# tactile_sensor_master.net
KiCad netlist of a schematic drawn in EAGLE
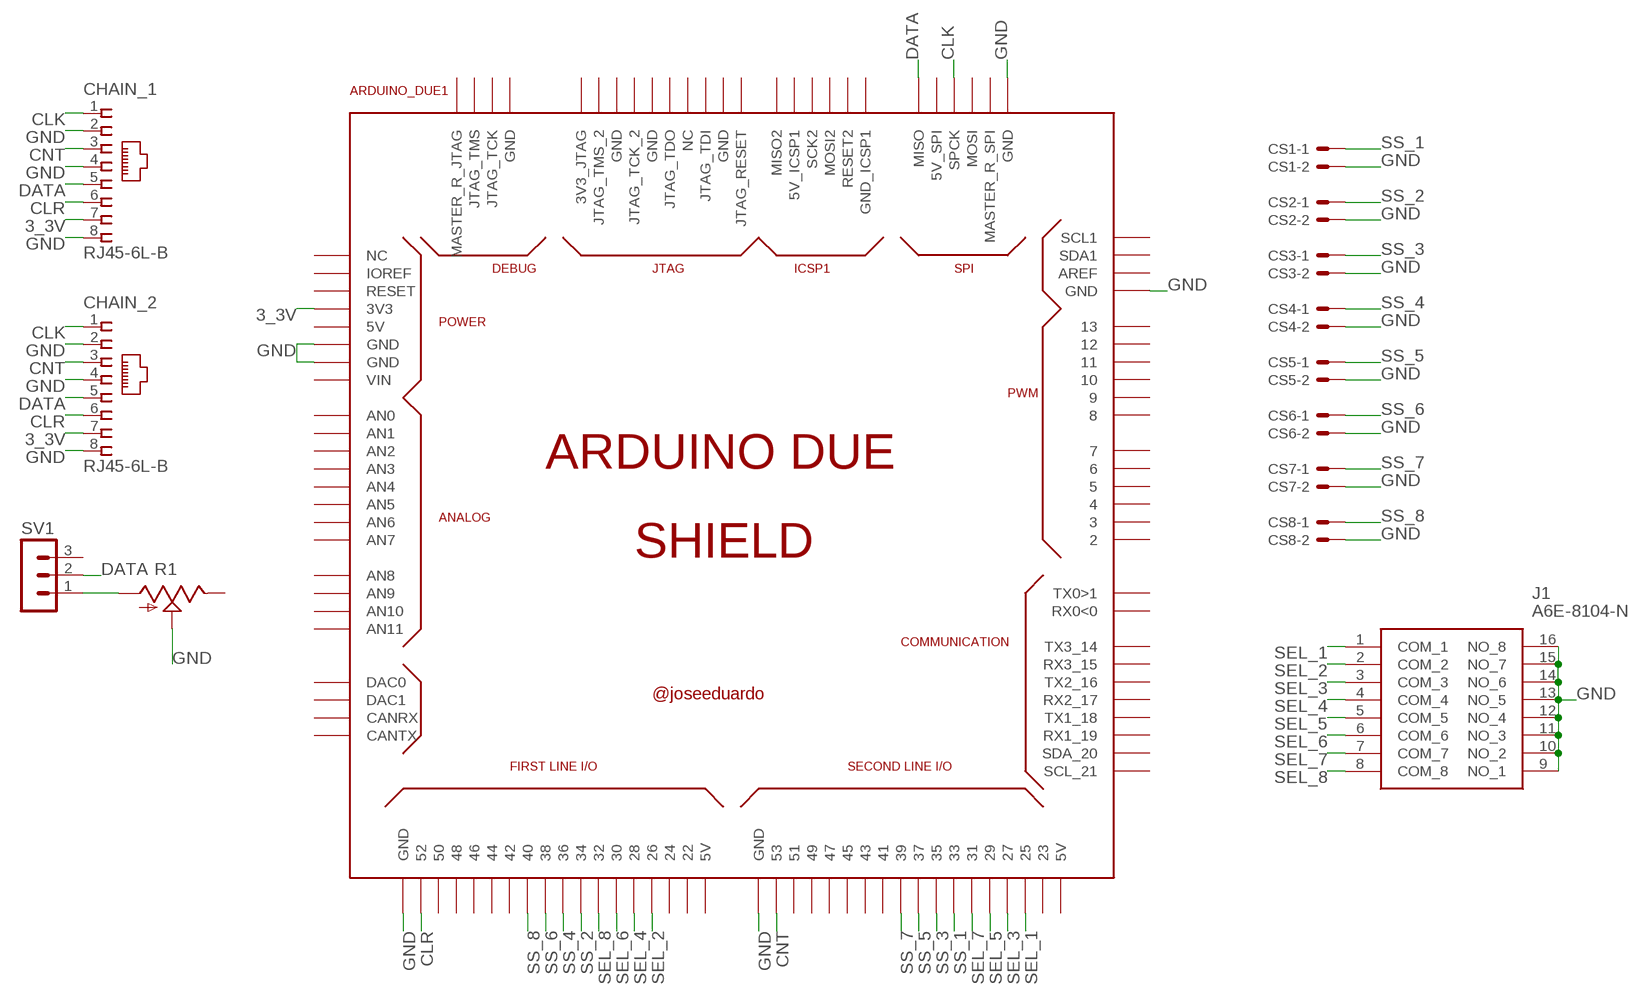
[diagram p0: schematic, sheet 1]

(export (version "E")
  (design (tool "Eeschema 10.0.6"))
  (components
    (comp (ref "ARDUINO_DUE1")
      (value "ARDUINO_DUE_SHIELD")
      (footprint "eagle-import:ARDUINO_DUE_SHIELD")
      (libsource (lib "eagle-import") (part "ARDUINO_DUE_SHIELD"))
    )
    (comp (ref "CHAIN_1")
      (value "RJ45-6L-B")
      (footprint "eagle-import:RJ45-NO-SHIELD")
      (libsource (lib "eagle-import") (part "RJ45-6L-B"))
    )
    (comp (ref "CHAIN_2")
      (value "RJ45-6L-B")
      (footprint "eagle-import:RJ45-NO-SHIELD")
      (libsource (lib "eagle-import") (part "RJ45-6L-B"))
    )
    (comp (ref "CS1")
      (value "22-23-2021")
      (footprint "eagle-import:22-23-2021")
      (fields (field (name "MF") "MOLEX"))
      (libsource (lib "eagle-import") (part "22-23-2021"))
    )
    (comp (ref "CS2")
      (value "22-23-2021")
      (footprint "eagle-import:22-23-2021")
      (fields (field (name "MF") "MOLEX"))
      (libsource (lib "eagle-import") (part "22-23-2021"))
    )
    (comp (ref "CS3")
      (value "22-23-2021")
      (footprint "eagle-import:22-23-2021")
      (fields (field (name "MF") "MOLEX"))
      (libsource (lib "eagle-import") (part "22-23-2021"))
    )
    (comp (ref "CS4")
      (value "22-23-2021")
      (footprint "eagle-import:22-23-2021")
      (fields (field (name "MF") "MOLEX"))
      (libsource (lib "eagle-import") (part "22-23-2021"))
    )
    (comp (ref "CS5")
      (value "22-23-2021")
      (footprint "eagle-import:22-23-2021")
      (fields (field (name "MF") "MOLEX"))
      (libsource (lib "eagle-import") (part "22-23-2021"))
    )
    (comp (ref "CS6")
      (value "22-23-2021")
      (footprint "eagle-import:22-23-2021")
      (fields (field (name "MF") "MOLEX"))
      (libsource (lib "eagle-import") (part "22-23-2021"))
    )
    (comp (ref "CS7")
      (value "22-23-2021")
      (footprint "eagle-import:22-23-2021")
      (fields (field (name "MF") "MOLEX"))
      (libsource (lib "eagle-import") (part "22-23-2021"))
    )
    (comp (ref "CS8")
      (value "22-23-2021")
      (footprint "eagle-import:22-23-2021")
      (fields (field (name "MF") "MOLEX"))
      (libsource (lib "eagle-import") (part "22-23-2021"))
    )
    (comp (ref "J1")
      (value "A6E-8104-N")
      (footprint "eagle-import:A6E8104N")
      (fields (field (name "MOUSER_PART_NUMBER") "653-A6E8104N"))
      (libsource (lib "eagle-import") (part "A6E-8104-N"))
    )
    (comp (ref "R1")
      (value "TRIM_US-B25P")
      (footprint "eagle-import:B25P")
      (libsource (lib "eagle-import") (part "TRIM_US-B25P"))
    )
    (comp (ref "SV1")
      (value "MA03-1")
      (footprint "eagle-import:MA03-1")
      (libsource (lib "eagle-import") (part "MA03-1"))
    )
  )
  (nets
    (net (code "1") (name "/3_3V") (class "Default")
      (node (ref "ARDUINO_DUE1") (pin "3V3") (pinfunction "3V3_3V3") (pintype "bidirectional"))
      (node (ref "CHAIN_1") (pin "7") (pinfunction "7_7") (pintype "passive"))
      (node (ref "CHAIN_2") (pin "7") (pinfunction "7_7") (pintype "passive"))
    )
    (net (code "2") (name "/CLK") (class "Default")
      (node (ref "ARDUINO_DUE1") (pin "SPCK") (pinfunction "SPCK_SPCK") (pintype "bidirectional"))
      (node (ref "CHAIN_1") (pin "1") (pinfunction "1_1") (pintype "passive"))
      (node (ref "CHAIN_2") (pin "1") (pinfunction "1_1") (pintype "passive"))
    )
    (net (code "3") (name "/CLR") (class "Default")
      (node (ref "ARDUINO_DUE1") (pin "52") (pinfunction "52_52") (pintype "bidirectional"))
      (node (ref "CHAIN_1") (pin "6") (pinfunction "6_6") (pintype "passive"))
      (node (ref "CHAIN_2") (pin "6") (pinfunction "6_6") (pintype "passive"))
    )
    (net (code "4") (name "/CNT") (class "Default")
      (node (ref "ARDUINO_DUE1") (pin "53") (pinfunction "53_53") (pintype "bidirectional"))
      (node (ref "CHAIN_1") (pin "3") (pinfunction "3_3") (pintype "passive"))
      (node (ref "CHAIN_2") (pin "3") (pinfunction "3_3") (pintype "passive"))
    )
    (net (code "5") (name "/DATA") (class "Default")
      (node (ref "ARDUINO_DUE1") (pin "MISO") (pinfunction "MISO_MISO") (pintype "bidirectional"))
      (node (ref "CHAIN_1") (pin "5") (pinfunction "5_5") (pintype "passive"))
      (node (ref "CHAIN_2") (pin "5") (pinfunction "5_5") (pintype "passive"))
      (node (ref "SV1") (pin "2") (pinfunction "2_2") (pintype "passive"))
    )
    (net (code "6") (name "/GND") (class "Default")
      (node (ref "ARDUINO_DUE1") (pin "GND") (pinfunction "GND_GND") (pintype "bidirectional"))
      (node (ref "ARDUINO_DUE1") (pin "GND_1") (pinfunction "GND_GND_1") (pintype "bidirectional"))
      (node (ref "ARDUINO_DUE1") (pin "GND_2") (pinfunction "GND_GND_2") (pintype "bidirectional"))
      (node (ref "ARDUINO_DUE1") (pin "GND_3") (pinfunction "GND_GND_3") (pintype "bidirectional"))
      (node (ref "ARDUINO_DUE1") (pin "GND_4") (pinfunction "GND_GND_4") (pintype "bidirectional"))
      (node (ref "ARDUINO_DUE1") (pin "GND_5") (pinfunction "GND_GND_5") (pintype "bidirectional"))
      (node (ref "CHAIN_1") (pin "2") (pinfunction "2_2") (pintype "passive"))
      (node (ref "CHAIN_1") (pin "4") (pinfunction "4_4") (pintype "passive"))
      (node (ref "CHAIN_1") (pin "8") (pinfunction "8_8") (pintype "passive"))
      (node (ref "CHAIN_2") (pin "2") (pinfunction "2_2") (pintype "passive"))
      (node (ref "CHAIN_2") (pin "4") (pinfunction "4_4") (pintype "passive"))
      (node (ref "CHAIN_2") (pin "8") (pinfunction "8_8") (pintype "passive"))
      (node (ref "CS1") (pin "2") (pinfunction "S_2") (pintype "passive"))
      (node (ref "CS2") (pin "2") (pinfunction "S_2") (pintype "passive"))
      (node (ref "CS3") (pin "2") (pinfunction "S_2") (pintype "passive"))
      (node (ref "CS4") (pin "2") (pinfunction "S_2") (pintype "passive"))
      (node (ref "CS5") (pin "2") (pinfunction "S_2") (pintype "passive"))
      (node (ref "CS6") (pin "2") (pinfunction "S_2") (pintype "passive"))
      (node (ref "CS7") (pin "2") (pinfunction "S_2") (pintype "passive"))
      (node (ref "CS8") (pin "2") (pinfunction "S_2") (pintype "passive"))
      (node (ref "J1") (pin "10") (pinfunction "NO_2_10") (pintype "bidirectional"))
      (node (ref "J1") (pin "11") (pinfunction "NO_3_11") (pintype "bidirectional"))
      (node (ref "J1") (pin "12") (pinfunction "NO_4_12") (pintype "bidirectional"))
      (node (ref "J1") (pin "13") (pinfunction "NO_5_13") (pintype "bidirectional"))
      (node (ref "J1") (pin "14") (pinfunction "NO_6_14") (pintype "bidirectional"))
      (node (ref "J1") (pin "15") (pinfunction "NO_7_15") (pintype "bidirectional"))
      (node (ref "J1") (pin "16") (pinfunction "NO_8_16") (pintype "bidirectional"))
      (node (ref "J1") (pin "9") (pinfunction "NO_1_9") (pintype "bidirectional"))
      (node (ref "R1") (pin "S") (pinfunction "S_S") (pintype "passive"))
    )
    (net (code "7") (name "/SEL_1") (class "Default")
      (node (ref "ARDUINO_DUE1") (pin "25") (pinfunction "25_25") (pintype "bidirectional"))
      (node (ref "J1") (pin "1") (pinfunction "COM_1_1") (pintype "bidirectional"))
    )
    (net (code "8") (name "/SEL_2") (class "Default")
      (node (ref "ARDUINO_DUE1") (pin "26") (pinfunction "26_26") (pintype "bidirectional"))
      (node (ref "J1") (pin "2") (pinfunction "COM_2_2") (pintype "bidirectional"))
    )
    (net (code "9") (name "/SEL_3") (class "Default")
      (node (ref "ARDUINO_DUE1") (pin "27") (pinfunction "27_27") (pintype "bidirectional"))
      (node (ref "J1") (pin "3") (pinfunction "COM_3_3") (pintype "bidirectional"))
    )
    (net (code "10") (name "/SEL_4") (class "Default")
      (node (ref "ARDUINO_DUE1") (pin "28") (pinfunction "28_28") (pintype "bidirectional"))
      (node (ref "J1") (pin "4") (pinfunction "COM_4_4") (pintype "bidirectional"))
    )
    (net (code "11") (name "/SEL_5") (class "Default")
      (node (ref "ARDUINO_DUE1") (pin "29") (pinfunction "29_29") (pintype "bidirectional"))
      (node (ref "J1") (pin "5") (pinfunction "COM_5_5") (pintype "bidirectional"))
    )
    (net (code "12") (name "/SEL_6") (class "Default")
      (node (ref "ARDUINO_DUE1") (pin "30") (pinfunction "30_30") (pintype "bidirectional"))
      (node (ref "J1") (pin "6") (pinfunction "COM_6_6") (pintype "bidirectional"))
    )
    (net (code "13") (name "/SEL_7") (class "Default")
      (node (ref "ARDUINO_DUE1") (pin "31") (pinfunction "31_31") (pintype "bidirectional"))
      (node (ref "J1") (pin "7") (pinfunction "COM_7_7") (pintype "bidirectional"))
    )
    (net (code "14") (name "/SEL_8") (class "Default")
      (node (ref "ARDUINO_DUE1") (pin "32") (pinfunction "32_32") (pintype "bidirectional"))
      (node (ref "J1") (pin "8") (pinfunction "COM_8_8") (pintype "bidirectional"))
    )
    (net (code "15") (name "/SS_1") (class "Default")
      (node (ref "ARDUINO_DUE1") (pin "33") (pinfunction "33_33") (pintype "bidirectional"))
      (node (ref "CS1") (pin "1") (pinfunction "S_1") (pintype "passive"))
    )
    (net (code "16") (name "/SS_2") (class "Default")
      (node (ref "ARDUINO_DUE1") (pin "34") (pinfunction "34_34") (pintype "bidirectional"))
      (node (ref "CS2") (pin "1") (pinfunction "S_1") (pintype "passive"))
    )
    (net (code "17") (name "/SS_3") (class "Default")
      (node (ref "ARDUINO_DUE1") (pin "35") (pinfunction "35_35") (pintype "bidirectional"))
      (node (ref "CS3") (pin "1") (pinfunction "S_1") (pintype "passive"))
    )
    (net (code "18") (name "/SS_4") (class "Default")
      (node (ref "ARDUINO_DUE1") (pin "36") (pinfunction "36_36") (pintype "bidirectional"))
      (node (ref "CS4") (pin "1") (pinfunction "S_1") (pintype "passive"))
    )
    (net (code "19") (name "/SS_5") (class "Default")
      (node (ref "ARDUINO_DUE1") (pin "37") (pinfunction "37_37") (pintype "bidirectional"))
      (node (ref "CS5") (pin "1") (pinfunction "S_1") (pintype "passive"))
    )
    (net (code "20") (name "/SS_6") (class "Default")
      (node (ref "ARDUINO_DUE1") (pin "38") (pinfunction "38_38") (pintype "bidirectional"))
      (node (ref "CS6") (pin "1") (pinfunction "S_1") (pintype "passive"))
    )
    (net (code "21") (name "/SS_7") (class "Default")
      (node (ref "ARDUINO_DUE1") (pin "39") (pinfunction "39_39") (pintype "bidirectional"))
      (node (ref "CS7") (pin "1") (pinfunction "S_1") (pintype "passive"))
    )
    (net (code "22") (name "/SS_8") (class "Default")
      (node (ref "ARDUINO_DUE1") (pin "40") (pinfunction "40_40") (pintype "bidirectional"))
      (node (ref "CS8") (pin "1") (pinfunction "S_1") (pintype "passive"))
    )
    (net (code "23") (name "Net-(R1-PadA)") (class "Default")
      (node (ref "R1") (pin "A") (pinfunction "A_A") (pintype "passive"))
      (node (ref "SV1") (pin "1") (pinfunction "1_1") (pintype "passive"))
    )
    (net (code "24") (name "unconnected-(ARDUINO_DUE1-5V-Pad5V0)") (class "Default")
      (node (ref "ARDUINO_DUE1") (pin "5V0") (pinfunction "5V_5V0") (pintype "bidirectional"))
    )
    (net (code "25") (name "unconnected-(ARDUINO_DUE1-5V-Pad5V0_1)") (class "Default")
      (node (ref "ARDUINO_DUE1") (pin "5V0_1") (pinfunction "5V_5V0_1") (pintype "bidirectional"))
    )
    (net (code "26") (name "unconnected-(ARDUINO_DUE1-5V-Pad5V0_2)") (class "Default")
      (node (ref "ARDUINO_DUE1") (pin "5V0_2") (pinfunction "5V_5V0_2") (pintype "bidirectional"))
    )
    (net (code "27") (name "unconnected-(ARDUINO_DUE1-5V_SPI-Pad5V_2)") (class "Default")
      (node (ref "ARDUINO_DUE1") (pin "5V_2") (pinfunction "5V_SPI_5V_2") (pintype "bidirectional"))
    )
    (net (code "28") (name "unconnected-(ARDUINO_DUE1-AN0-PadA0)") (class "Default")
      (node (ref "ARDUINO_DUE1") (pin "A0") (pinfunction "AN0_A0") (pintype "bidirectional"))
    )
    (net (code "29") (name "unconnected-(ARDUINO_DUE1-AN1-PadA1)") (class "Default")
      (node (ref "ARDUINO_DUE1") (pin "A1") (pinfunction "AN1_A1") (pintype "bidirectional"))
    )
    (net (code "30") (name "unconnected-(ARDUINO_DUE1-AN2-PadA2)") (class "Default")
      (node (ref "ARDUINO_DUE1") (pin "A2") (pinfunction "AN2_A2") (pintype "bidirectional"))
    )
    (net (code "31") (name "unconnected-(ARDUINO_DUE1-AN3-PadA3)") (class "Default")
      (node (ref "ARDUINO_DUE1") (pin "A3") (pinfunction "AN3_A3") (pintype "bidirectional"))
    )
    (net (code "32") (name "unconnected-(ARDUINO_DUE1-AN4-PadA4)") (class "Default")
      (node (ref "ARDUINO_DUE1") (pin "A4") (pinfunction "AN4_A4") (pintype "bidirectional"))
    )
    (net (code "33") (name "unconnected-(ARDUINO_DUE1-AN5-PadA5)") (class "Default")
      (node (ref "ARDUINO_DUE1") (pin "A5") (pinfunction "AN5_A5") (pintype "bidirectional"))
    )
    (net (code "34") (name "unconnected-(ARDUINO_DUE1-AN6-PadA6)") (class "Default")
      (node (ref "ARDUINO_DUE1") (pin "A6") (pinfunction "AN6_A6") (pintype "bidirectional"))
    )
    (net (code "35") (name "unconnected-(ARDUINO_DUE1-AN7-PadA7)") (class "Default")
      (node (ref "ARDUINO_DUE1") (pin "A7") (pinfunction "AN7_A7") (pintype "bidirectional"))
    )
    (net (code "36") (name "unconnected-(ARDUINO_DUE1-AN8-PadA8)") (class "Default")
      (node (ref "ARDUINO_DUE1") (pin "A8") (pinfunction "AN8_A8") (pintype "bidirectional"))
    )
    (net (code "37") (name "unconnected-(ARDUINO_DUE1-AN9-PadA9)") (class "Default")
      (node (ref "ARDUINO_DUE1") (pin "A9") (pinfunction "AN9_A9") (pintype "bidirectional"))
    )
    (net (code "38") (name "unconnected-(ARDUINO_DUE1-AN10-PadA10)") (class "Default")
      (node (ref "ARDUINO_DUE1") (pin "A10") (pinfunction "AN10_A10") (pintype "bidirectional"))
    )
    (net (code "39") (name "unconnected-(ARDUINO_DUE1-AN11-PadA11)") (class "Default")
      (node (ref "ARDUINO_DUE1") (pin "A11") (pinfunction "AN11_A11") (pintype "bidirectional"))
    )
    (net (code "40") (name "unconnected-(ARDUINO_DUE1-GND-PadGND_7)") (class "Default")
      (node (ref "ARDUINO_DUE1") (pin "GND_7") (pinfunction "GND_GND_7") (pintype "bidirectional"))
    )
    (net (code "41") (name "unconnected-(ARDUINO_DUE1-GND-PadGND_8)") (class "Default")
      (node (ref "ARDUINO_DUE1") (pin "GND_8") (pinfunction "GND_GND_8") (pintype "bidirectional"))
    )
    (net (code "42") (name "unconnected-(ARDUINO_DUE1-GND-PadGND_9)") (class "Default")
      (node (ref "ARDUINO_DUE1") (pin "GND_9") (pinfunction "GND_GND_9") (pintype "bidirectional"))
    )
    (net (code "43") (name "unconnected-(ARDUINO_DUE1-GND-PadGND_10)") (class "Default")
      (node (ref "ARDUINO_DUE1") (pin "GND_10") (pinfunction "GND_GND_10") (pintype "bidirectional"))
    )
    (net (code "44") (name "unconnected-(ARDUINO_DUE1-MASTER_R_JTAG-PadMASTER_RESET_JTAG)") (class "Default")
      (node (ref "ARDUINO_DUE1") (pin "MASTER_RESET_JTAG") (pinfunction "MASTER_R_JTAG_MASTER_RESET_JTAG") (pintype "bidirectional"))
    )
    (net (code "45") (name "unconnected-(ARDUINO_DUE1-MASTER_R_SPI-PadMASTER_RESET_SPI)") (class "Default")
      (node (ref "ARDUINO_DUE1") (pin "MASTER_RESET_SPI") (pinfunction "MASTER_R_SPI_MASTER_RESET_SPI") (pintype "bidirectional"))
    )
    (net (code "46") (name "unconnected-(ARDUINO_DUE1-NC-PadNC_2)") (class "Default")
      (node (ref "ARDUINO_DUE1") (pin "NC_2") (pinfunction "NC_NC_2") (pintype "no_connect"))
    )
    (net (code "47") (name "unconnected-(ARDUINO_DUE1-NC-PadNC_5)") (class "Default")
      (node (ref "ARDUINO_DUE1") (pin "NC_5") (pinfunction "NC_NC_5") (pintype "bidirectional"))
    )
    (net (code "48") (name "unconnected-(ARDUINO_DUE1-Pad2)") (class "Default")
      (node (ref "ARDUINO_DUE1") (pin "2") (pinfunction "2_2") (pintype "bidirectional"))
    )
    (net (code "49") (name "unconnected-(ARDUINO_DUE1-Pad3)") (class "Default")
      (node (ref "ARDUINO_DUE1") (pin "3") (pinfunction "3_3") (pintype "bidirectional"))
    )
    (net (code "50") (name "unconnected-(ARDUINO_DUE1-Pad3V3_JTAG)") (class "Default")
      (node (ref "ARDUINO_DUE1") (pin "3V3_JTAG") (pinfunction "3V3_JTAG_3V3_JTAG") (pintype "bidirectional"))
    )
    (net (code "51") (name "unconnected-(ARDUINO_DUE1-Pad4)") (class "Default")
      (node (ref "ARDUINO_DUE1") (pin "4") (pinfunction "4_4") (pintype "bidirectional"))
    )
    (net (code "52") (name "unconnected-(ARDUINO_DUE1-Pad5)") (class "Default")
      (node (ref "ARDUINO_DUE1") (pin "5") (pinfunction "5_5") (pintype "bidirectional"))
    )
    (net (code "53") (name "unconnected-(ARDUINO_DUE1-Pad5V_ICSP1)") (class "Default")
      (node (ref "ARDUINO_DUE1") (pin "5V_ICSP1") (pinfunction "5V_ICSP1_5V_ICSP1") (pintype "bidirectional"))
    )
    (net (code "54") (name "unconnected-(ARDUINO_DUE1-Pad6)") (class "Default")
      (node (ref "ARDUINO_DUE1") (pin "6") (pinfunction "6_6") (pintype "bidirectional"))
    )
    (net (code "55") (name "unconnected-(ARDUINO_DUE1-Pad7)") (class "Default")
      (node (ref "ARDUINO_DUE1") (pin "7") (pinfunction "7_7") (pintype "bidirectional"))
    )
    (net (code "56") (name "unconnected-(ARDUINO_DUE1-Pad8)") (class "Default")
      (node (ref "ARDUINO_DUE1") (pin "8") (pinfunction "8_8") (pintype "bidirectional"))
    )
    (net (code "57") (name "unconnected-(ARDUINO_DUE1-Pad9)") (class "Default")
      (node (ref "ARDUINO_DUE1") (pin "9") (pinfunction "9_9") (pintype "bidirectional"))
    )
    (net (code "58") (name "unconnected-(ARDUINO_DUE1-Pad10)") (class "Default")
      (node (ref "ARDUINO_DUE1") (pin "10") (pinfunction "10_10") (pintype "bidirectional"))
    )
    (net (code "59") (name "unconnected-(ARDUINO_DUE1-Pad11)") (class "Default")
      (node (ref "ARDUINO_DUE1") (pin "11") (pinfunction "11_11") (pintype "bidirectional"))
    )
    (net (code "60") (name "unconnected-(ARDUINO_DUE1-Pad12)") (class "Default")
      (node (ref "ARDUINO_DUE1") (pin "12") (pinfunction "12_12") (pintype "bidirectional"))
    )
    (net (code "61") (name "unconnected-(ARDUINO_DUE1-Pad13)") (class "Default")
      (node (ref "ARDUINO_DUE1") (pin "13") (pinfunction "13_13") (pintype "bidirectional"))
    )
    (net (code "62") (name "unconnected-(ARDUINO_DUE1-Pad22)") (class "Default")
      (node (ref "ARDUINO_DUE1") (pin "22") (pinfunction "22_22") (pintype "bidirectional"))
    )
    (net (code "63") (name "unconnected-(ARDUINO_DUE1-Pad23)") (class "Default")
      (node (ref "ARDUINO_DUE1") (pin "23") (pinfunction "23_23") (pintype "bidirectional"))
    )
    (net (code "64") (name "unconnected-(ARDUINO_DUE1-Pad24)") (class "Default")
      (node (ref "ARDUINO_DUE1") (pin "24") (pinfunction "24_24") (pintype "bidirectional"))
    )
    (net (code "65") (name "unconnected-(ARDUINO_DUE1-Pad41)") (class "Default")
      (node (ref "ARDUINO_DUE1") (pin "41") (pinfunction "41_41") (pintype "bidirectional"))
    )
    (net (code "66") (name "unconnected-(ARDUINO_DUE1-Pad42)") (class "Default")
      (node (ref "ARDUINO_DUE1") (pin "42") (pinfunction "42_42") (pintype "bidirectional"))
    )
    (net (code "67") (name "unconnected-(ARDUINO_DUE1-Pad43)") (class "Default")
      (node (ref "ARDUINO_DUE1") (pin "43") (pinfunction "43_43") (pintype "bidirectional"))
    )
    (net (code "68") (name "unconnected-(ARDUINO_DUE1-Pad44)") (class "Default")
      (node (ref "ARDUINO_DUE1") (pin "44") (pinfunction "44_44") (pintype "bidirectional"))
    )
    (net (code "69") (name "unconnected-(ARDUINO_DUE1-Pad45)") (class "Default")
      (node (ref "ARDUINO_DUE1") (pin "45") (pinfunction "45_45") (pintype "bidirectional"))
    )
    (net (code "70") (name "unconnected-(ARDUINO_DUE1-Pad46)") (class "Default")
      (node (ref "ARDUINO_DUE1") (pin "46") (pinfunction "46_46") (pintype "bidirectional"))
    )
    (net (code "71") (name "unconnected-(ARDUINO_DUE1-Pad47)") (class "Default")
      (node (ref "ARDUINO_DUE1") (pin "47") (pinfunction "47_47") (pintype "bidirectional"))
    )
    (net (code "72") (name "unconnected-(ARDUINO_DUE1-Pad48)") (class "Default")
      (node (ref "ARDUINO_DUE1") (pin "48") (pinfunction "48_48") (pintype "bidirectional"))
    )
    (net (code "73") (name "unconnected-(ARDUINO_DUE1-Pad49)") (class "Default")
      (node (ref "ARDUINO_DUE1") (pin "49") (pinfunction "49_49") (pintype "bidirectional"))
    )
    (net (code "74") (name "unconnected-(ARDUINO_DUE1-Pad50)") (class "Default")
      (node (ref "ARDUINO_DUE1") (pin "50") (pinfunction "50_50") (pintype "bidirectional"))
    )
    (net (code "75") (name "unconnected-(ARDUINO_DUE1-Pad51)") (class "Default")
      (node (ref "ARDUINO_DUE1") (pin "51") (pinfunction "51_51") (pintype "bidirectional"))
    )
    (net (code "76") (name "unconnected-(ARDUINO_DUE1-PadAREF)") (class "Default")
      (node (ref "ARDUINO_DUE1") (pin "AREF") (pinfunction "AREF_AREF") (pintype "bidirectional"))
    )
    (net (code "77") (name "unconnected-(ARDUINO_DUE1-PadCANRX)") (class "Default")
      (node (ref "ARDUINO_DUE1") (pin "CANRX") (pinfunction "CANRX_CANRX") (pintype "bidirectional"))
    )
    (net (code "78") (name "unconnected-(ARDUINO_DUE1-PadCANTX)") (class "Default")
      (node (ref "ARDUINO_DUE1") (pin "CANTX") (pinfunction "CANTX_CANTX") (pintype "bidirectional"))
    )
    (net (code "79") (name "unconnected-(ARDUINO_DUE1-PadDAC0)") (class "Default")
      (node (ref "ARDUINO_DUE1") (pin "DAC0") (pinfunction "DAC0_DAC0") (pintype "bidirectional"))
    )
    (net (code "80") (name "unconnected-(ARDUINO_DUE1-PadDAC1)") (class "Default")
      (node (ref "ARDUINO_DUE1") (pin "DAC1") (pinfunction "DAC1_DAC1") (pintype "bidirectional"))
    )
    (net (code "81") (name "unconnected-(ARDUINO_DUE1-PadGND_ICSP1)") (class "Default")
      (node (ref "ARDUINO_DUE1") (pin "GND_ICSP1") (pinfunction "GND_ICSP1_GND_ICSP1") (pintype "bidirectional"))
    )
    (net (code "82") (name "unconnected-(ARDUINO_DUE1-PadIOREF)") (class "Default")
      (node (ref "ARDUINO_DUE1") (pin "IOREF") (pinfunction "IOREF_IOREF") (pintype "bidirectional"))
    )
    (net (code "83") (name "unconnected-(ARDUINO_DUE1-PadJTAG_RESET)") (class "Default")
      (node (ref "ARDUINO_DUE1") (pin "JTAG_RESET") (pinfunction "JTAG_RESET_JTAG_RESET") (pintype "bidirectional"))
    )
    (net (code "84") (name "unconnected-(ARDUINO_DUE1-PadJTAG_TCK)") (class "Default")
      (node (ref "ARDUINO_DUE1") (pin "JTAG_TCK") (pinfunction "JTAG_TCK_JTAG_TCK") (pintype "bidirectional"))
    )
    (net (code "85") (name "unconnected-(ARDUINO_DUE1-PadJTAG_TCK_2)") (class "Default")
      (node (ref "ARDUINO_DUE1") (pin "JTAG_TCK_2") (pinfunction "JTAG_TCK_2_JTAG_TCK_2") (pintype "bidirectional"))
    )
    (net (code "86") (name "unconnected-(ARDUINO_DUE1-PadJTAG_TDI)") (class "Default")
      (node (ref "ARDUINO_DUE1") (pin "JTAG_TDI") (pinfunction "JTAG_TDI_JTAG_TDI") (pintype "bidirectional"))
    )
    (net (code "87") (name "unconnected-(ARDUINO_DUE1-PadJTAG_TDO)") (class "Default")
      (node (ref "ARDUINO_DUE1") (pin "JTAG_TDO") (pinfunction "JTAG_TDO_JTAG_TDO") (pintype "bidirectional"))
    )
    (net (code "88") (name "unconnected-(ARDUINO_DUE1-PadJTAG_TMS)") (class "Default")
      (node (ref "ARDUINO_DUE1") (pin "JTAG_TMS") (pinfunction "JTAG_TMS_JTAG_TMS") (pintype "bidirectional"))
    )
    (net (code "89") (name "unconnected-(ARDUINO_DUE1-PadJTAG_TMS_2)") (class "Default")
      (node (ref "ARDUINO_DUE1") (pin "JTAG_TMS_2") (pinfunction "JTAG_TMS_2_JTAG_TMS_2") (pintype "bidirectional"))
    )
    (net (code "90") (name "unconnected-(ARDUINO_DUE1-PadMISO2)") (class "Default")
      (node (ref "ARDUINO_DUE1") (pin "MISO2") (pinfunction "MISO2_MISO2") (pintype "bidirectional"))
    )
    (net (code "91") (name "unconnected-(ARDUINO_DUE1-PadMOSI)") (class "Default")
      (node (ref "ARDUINO_DUE1") (pin "MOSI") (pinfunction "MOSI_MOSI") (pintype "bidirectional"))
    )
    (net (code "92") (name "unconnected-(ARDUINO_DUE1-PadMOSI2)") (class "Default")
      (node (ref "ARDUINO_DUE1") (pin "MOSI2") (pinfunction "MOSI2_MOSI2") (pintype "bidirectional"))
    )
    (net (code "93") (name "unconnected-(ARDUINO_DUE1-PadRESET)") (class "Default")
      (node (ref "ARDUINO_DUE1") (pin "RESET") (pinfunction "RESET_RESET") (pintype "bidirectional"))
    )
    (net (code "94") (name "unconnected-(ARDUINO_DUE1-PadRESET2)") (class "Default")
      (node (ref "ARDUINO_DUE1") (pin "RESET2") (pinfunction "RESET2_RESET2") (pintype "bidirectional"))
    )
    (net (code "95") (name "unconnected-(ARDUINO_DUE1-PadSCK2)") (class "Default")
      (node (ref "ARDUINO_DUE1") (pin "SCK2") (pinfunction "SCK2_SCK2") (pintype "bidirectional"))
    )
    (net (code "96") (name "unconnected-(ARDUINO_DUE1-PadSCL1)") (class "Default")
      (node (ref "ARDUINO_DUE1") (pin "SCL1") (pinfunction "SCL1_SCL1") (pintype "bidirectional"))
    )
    (net (code "97") (name "unconnected-(ARDUINO_DUE1-PadSDA1)") (class "Default")
      (node (ref "ARDUINO_DUE1") (pin "SDA1") (pinfunction "SDA1_SDA1") (pintype "bidirectional"))
    )
    (net (code "98") (name "unconnected-(ARDUINO_DUE1-PadVIN)") (class "Default")
      (node (ref "ARDUINO_DUE1") (pin "VIN") (pinfunction "VIN_VIN") (pintype "bidirectional"))
    )
    (net (code "99") (name "unconnected-(ARDUINO_DUE1-RX0<0-Pad0)") (class "Default")
      (node (ref "ARDUINO_DUE1") (pin "0") (pinfunction "RX0<0_0") (pintype "bidirectional"))
    )
    (net (code "100") (name "unconnected-(ARDUINO_DUE1-RX1_19-Pad19)") (class "Default")
      (node (ref "ARDUINO_DUE1") (pin "19") (pinfunction "RX1_19_19") (pintype "bidirectional"))
    )
    (net (code "101") (name "unconnected-(ARDUINO_DUE1-RX2_17-Pad17)") (class "Default")
      (node (ref "ARDUINO_DUE1") (pin "17") (pinfunction "RX2_17_17") (pintype "bidirectional"))
    )
    (net (code "102") (name "unconnected-(ARDUINO_DUE1-RX3_15-Pad15)") (class "Default")
      (node (ref "ARDUINO_DUE1") (pin "15") (pinfunction "RX3_15_15") (pintype "bidirectional"))
    )
    (net (code "103") (name "unconnected-(ARDUINO_DUE1-SCL_21-Pad21)") (class "Default")
      (node (ref "ARDUINO_DUE1") (pin "21") (pinfunction "SCL_21_21") (pintype "bidirectional"))
    )
    (net (code "104") (name "unconnected-(ARDUINO_DUE1-SDA_20-Pad20)") (class "Default")
      (node (ref "ARDUINO_DUE1") (pin "20") (pinfunction "SDA_20_20") (pintype "bidirectional"))
    )
    (net (code "105") (name "unconnected-(ARDUINO_DUE1-TX0>1-Pad1)") (class "Default")
      (node (ref "ARDUINO_DUE1") (pin "1") (pinfunction "TX0>1_1") (pintype "bidirectional"))
    )
    (net (code "106") (name "unconnected-(ARDUINO_DUE1-TX1_18-Pad18)") (class "Default")
      (node (ref "ARDUINO_DUE1") (pin "18") (pinfunction "TX1_18_18") (pintype "bidirectional"))
    )
    (net (code "107") (name "unconnected-(ARDUINO_DUE1-TX2_16-Pad16)") (class "Default")
      (node (ref "ARDUINO_DUE1") (pin "16") (pinfunction "TX2_16_16") (pintype "bidirectional"))
    )
    (net (code "108") (name "unconnected-(ARDUINO_DUE1-TX3_14-Pad14)") (class "Default")
      (node (ref "ARDUINO_DUE1") (pin "14") (pinfunction "TX3_14_14") (pintype "bidirectional"))
    )
    (net (code "109") (name "unconnected-(R1-PadE)") (class "Default")
      (node (ref "R1") (pin "E") (pinfunction "E_E") (pintype "passive"))
    )
    (net (code "110") (name "unconnected-(SV1-Pad3)") (class "Default")
      (node (ref "SV1") (pin "3") (pinfunction "3_3") (pintype "passive"))
    )
  )
)
